# SurfacePressureSensor_V2.net
KiCad netlist of a schematic drawn in Altium Designer
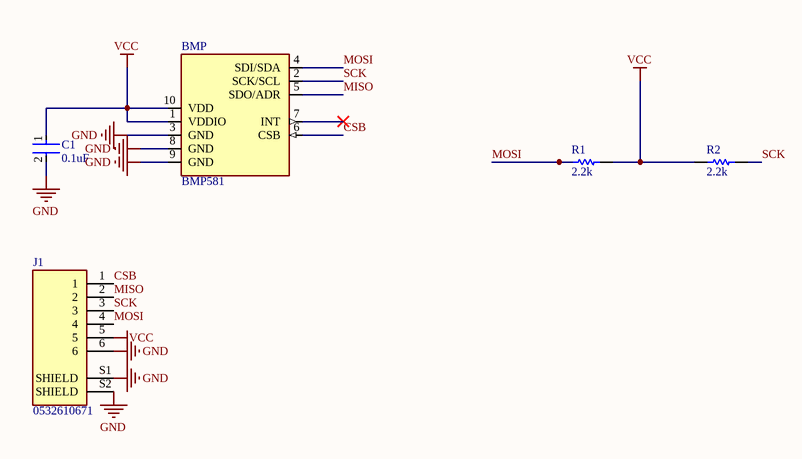
[diagram p0: SurfacePressureSensor_V2.SchDoc]

(export (version "E")
  (design (tool "Eeschema 10.0.6"))
  (components
    (comp (ref "BMP")
      (value "BMP581")
      (footprint "BMP581")
      (fields (field (name "MF") "Bosch"))
      (libsource (lib "BMP581") (part "BMP581"))
    )
    (comp (ref "C1")
      (value "0.1uF")
      (footprint "FP-C0805C-DG-MFG")
      (description "CAP CER 10UF 10V X5R 0805")
      (fields (field (name "TOLERANCE") "10%") (field (name "MANUFACTURER PART NUMBER") "C0805C106K8PACTU"))
      (libsource (lib "Altium Content Vault") (part "11868f565c42a9108669ba33697ecf6"))
    )
    (comp (ref "J1")
      (value "0532610671")
      (footprint "MOLEX_0532610671")
      (description "Picoblade Connector, 6 Circuit Single Row, Right Angle Surface Mount SMT PCB")
      (fields (field (name "DIGI-KEY_PART_NUMBER") "WM7624CT-ND") (field (name "MF") "Molex"))
      (libsource (lib "0532610671") (part "0532610671"))
    )
    (comp (ref "R1")
      (value "2.2k")
      (footprint "RESC2013X50X30LL20T20")
      (fields (field (name "MANUFACTURER") "Vishay Dale") (field (name "PART NUMBER") "CRCW08050000Z0EA"))
      (libsource (lib "Altium Content Vault") (part "RES"))
    )
    (comp (ref "R2")
      (value "2.2k")
      (footprint "RESC2013X50X30LL20T20")
      (fields (field (name "MANUFACTURER") "Vishay Dale") (field (name "PART NUMBER") "CRCW08050000Z0EA"))
      (libsource (lib "Altium Content Vault") (part "RES"))
    )
  )
  (nets
    (net (code "1") (name "/CSB") (class "Default")
      (node (ref "BMP") (pin "6") (pinfunction "CSB_6") (pintype "input"))
      (node (ref "J1") (pin "1") (pinfunction "1_1") (pintype "passive"))
    )
    (net (code "2") (name "/MISO") (class "Default")
      (node (ref "BMP") (pin "5") (pinfunction "SDO/ADR_5") (pintype "bidirectional"))
      (node (ref "J1") (pin "2") (pinfunction "2_2") (pintype "passive"))
    )
    (net (code "3") (name "/MOSI") (class "Default")
      (node (ref "BMP") (pin "4") (pinfunction "SDI/SDA_4") (pintype "bidirectional"))
      (node (ref "J1") (pin "4") (pinfunction "4_4") (pintype "passive"))
      (node (ref "R1") (pin "1") (pinfunction "1_1") (pintype "passive"))
    )
    (net (code "4") (name "/SCK") (class "Default")
      (node (ref "BMP") (pin "2") (pinfunction "SCK/SCL_2") (pintype "bidirectional"))
      (node (ref "J1") (pin "3") (pinfunction "3_3") (pintype "passive"))
      (node (ref "R2") (pin "2") (pinfunction "2_2") (pintype "passive"))
    )
    (net (code "5") (name "GND") (class "Default")
      (node (ref "BMP") (pin "3") (pinfunction "GND_3") (pintype "power_in"))
      (node (ref "BMP") (pin "8") (pinfunction "GND_8") (pintype "power_in"))
      (node (ref "BMP") (pin "9") (pinfunction "GND_9") (pintype "power_in"))
      (node (ref "C1") (pin "2") (pinfunction "2_2") (pintype "passive"))
      (node (ref "J1") (pin "6") (pinfunction "6_6") (pintype "passive"))
      (node (ref "J1") (pin "S1") (pinfunction "SHIELD_S1") (pintype "passive"))
      (node (ref "J1") (pin "S2") (pinfunction "SHIELD_S2") (pintype "passive"))
    )
    (net (code "6") (name "VCC") (class "Default")
      (node (ref "BMP") (pin "1") (pinfunction "VDDIO_1") (pintype "power_in"))
      (node (ref "BMP") (pin "10") (pinfunction "VDD_10") (pintype "power_in"))
      (node (ref "C1") (pin "1") (pinfunction "1_1") (pintype "passive"))
      (node (ref "J1") (pin "5") (pinfunction "5_5") (pintype "passive"))
      (node (ref "R1") (pin "2") (pinfunction "2_2") (pintype "passive"))
      (node (ref "R2") (pin "1") (pinfunction "1_1") (pintype "passive"))
    )
    (net (code "7") (name "unconnected-(BMP-INT-Pad7)") (class "Default")
      (node (ref "BMP") (pin "7") (pinfunction "INT_7") (pintype "output+no_connect"))
    )
  )
)
